# lichtenstein_controller.net
KiCad netlist of a schematic drawn in EAGLE
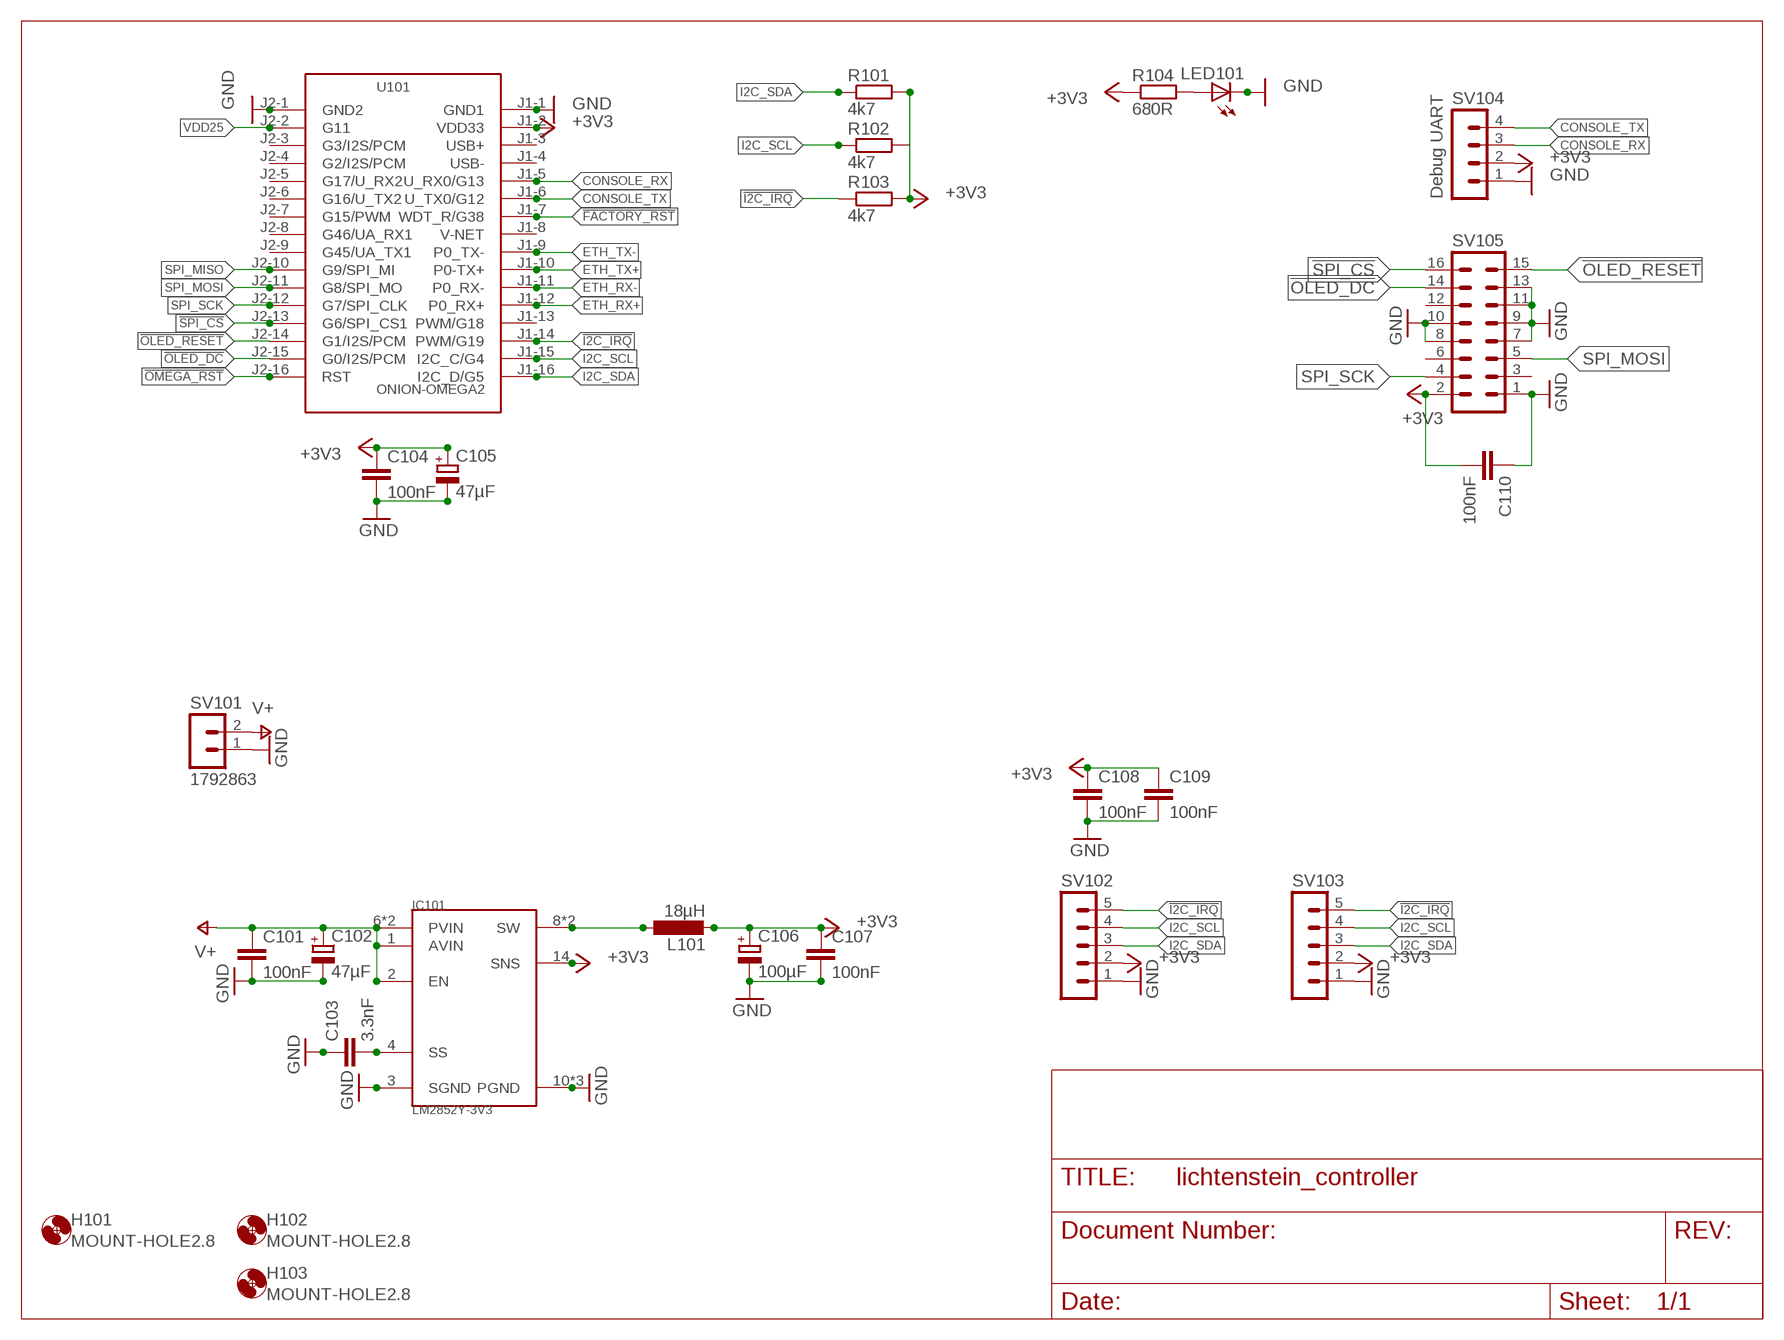
[diagram p0: schematic, sheet 1]

(export (version "E")
  (design (tool "Eeschema 10.0.6"))
  (components
    (comp (ref "C101")
      (value "100nF")
      (footprint "eagle-import:C0805")
      (libsource (lib "eagle-import") (part "C-EUC0805"))
    )
    (comp (ref "C102")
      (value "47µF")
      (footprint "eagle-import:CT7343")
      (libsource (lib "eagle-import") (part "CPOL-EUCT7343"))
    )
    (comp (ref "C103")
      (value "3.3nF")
      (footprint "eagle-import:C0805")
      (libsource (lib "eagle-import") (part "C-EUC0805"))
    )
    (comp (ref "C104")
      (value "100nF")
      (footprint "eagle-import:C0805")
      (libsource (lib "eagle-import") (part "C-EUC0805"))
    )
    (comp (ref "C105")
      (value "47µF")
      (footprint "eagle-import:CT7343")
      (libsource (lib "eagle-import") (part "CPOL-EUCT7343"))
    )
    (comp (ref "C106")
      (value "100µF")
      (footprint "eagle-import:CT7343")
      (libsource (lib "eagle-import") (part "CPOL-EUCT7343"))
    )
    (comp (ref "C107")
      (value "100nF")
      (footprint "eagle-import:C0805")
      (libsource (lib "eagle-import") (part "C-EUC0805"))
    )
    (comp (ref "C108")
      (value "100nF")
      (footprint "eagle-import:C0805")
      (libsource (lib "eagle-import") (part "C-EUC0805"))
    )
    (comp (ref "C109")
      (value "100nF")
      (footprint "eagle-import:C0805")
      (libsource (lib "eagle-import") (part "C-EUC0805"))
    )
    (comp (ref "C110")
      (value "100nF")
      (footprint "eagle-import:C0805")
      (libsource (lib "eagle-import") (part "C-EUC0805"))
    )
    (comp (ref "H101")
      (value "MOUNT-HOLE2.8")
      (footprint "eagle-import:2,8")
      (libsource (lib "eagle-import") (part "MOUNT-HOLE2.8"))
    )
    (comp (ref "H102")
      (value "MOUNT-HOLE2.8")
      (footprint "eagle-import:2,8")
      (libsource (lib "eagle-import") (part "MOUNT-HOLE2.8"))
    )
    (comp (ref "H103")
      (value "MOUNT-HOLE2.8")
      (footprint "eagle-import:2,8")
      (libsource (lib "eagle-import") (part "MOUNT-HOLE2.8"))
    )
    (comp (ref "IC101")
      (value "LM2852Y-3V3")
      (footprint "eagle-import:HTSSOP14")
      (libsource (lib "eagle-import") (part "LM2852HTSSOP14"))
    )
    (comp (ref "L101")
      (value "18µH")
      (footprint "eagle-import:SRR1050A")
      (libsource (lib "eagle-import") (part "SRR1050A"))
    )
    (comp (ref "LED101")
      (value "LEDCHIPLED_1206")
      (footprint "eagle-import:CHIPLED_1206")
      (libsource (lib "eagle-import") (part "LEDCHIPLED_1206"))
    )
    (comp (ref "R101")
      (value "4k7")
      (footprint "eagle-import:M0805")
      (libsource (lib "eagle-import") (part "R-EU_M0805"))
    )
    (comp (ref "R102")
      (value "4k7")
      (footprint "eagle-import:M0805")
      (libsource (lib "eagle-import") (part "R-EU_M0805"))
    )
    (comp (ref "R103")
      (value "4k7")
      (footprint "eagle-import:M0805")
      (libsource (lib "eagle-import") (part "R-EU_M0805"))
    )
    (comp (ref "R104")
      (value "680R")
      (footprint "eagle-import:M0805")
      (libsource (lib "eagle-import") (part "R-EU_M0805"))
    )
    (comp (ref "SV101")
      (value "1792863")
      (footprint "eagle-import:1792863")
      (libsource (lib "eagle-import") (part "1792863"))
    )
    (comp (ref "SV102")
      (value "MA05-1")
      (footprint "eagle-import:MA05-1")
      (libsource (lib "eagle-import") (part "MA05-1"))
    )
    (comp (ref "SV103")
      (value "MA05-1")
      (footprint "eagle-import:MA05-1")
      (libsource (lib "eagle-import") (part "MA05-1"))
    )
    (comp (ref "SV104")
      (value "MA04-1")
      (footprint "eagle-import:MA04-1")
      (libsource (lib "eagle-import") (part "MA04-1"))
    )
    (comp (ref "SV105")
      (value "MA08-2")
      (footprint "eagle-import:MA08-2")
      (libsource (lib "eagle-import") (part "MA08-2"))
    )
    (comp (ref "U101")
      (value "ONION-OMEGA2")
      (footprint "eagle-import:ONION-2MM-2X16")
      (libsource (lib "eagle-import") (part "ONION-OMEGA2"))
    )
  )
  (nets
    (net (code "1") (name "+3V3") (class "Default")
      (node (ref "C104") (pin "1") (pinfunction "1_1") (pintype "passive"))
      (node (ref "C105") (pin "+") (pinfunction "+_+") (pintype "passive"))
      (node (ref "C106") (pin "+") (pinfunction "+_+") (pintype "passive"))
      (node (ref "C107") (pin "1") (pinfunction "1_1") (pintype "passive"))
      (node (ref "C108") (pin "1") (pinfunction "1_1") (pintype "passive"))
      (node (ref "C109") (pin "1") (pinfunction "1_1") (pintype "passive"))
      (node (ref "C110") (pin "2") (pinfunction "2_2") (pintype "passive"))
      (node (ref "IC101") (pin "14") (pinfunction "SNS_14") (pintype "bidirectional"))
      (node (ref "L101") (pin "P$2") (pinfunction "2_P$2") (pintype "passive"))
      (node (ref "R101") (pin "2") (pinfunction "2_2") (pintype "passive"))
      (node (ref "R102") (pin "2") (pinfunction "2_2") (pintype "passive"))
      (node (ref "R103") (pin "2") (pinfunction "2_2") (pintype "passive"))
      (node (ref "R104") (pin "1") (pinfunction "1_1") (pintype "passive"))
      (node (ref "SV102") (pin "2") (pinfunction "2_2") (pintype "passive"))
      (node (ref "SV103") (pin "2") (pinfunction "2_2") (pintype "passive"))
      (node (ref "SV104") (pin "2") (pinfunction "2_2") (pintype "passive"))
      (node (ref "SV105") (pin "2") (pinfunction "2_2") (pintype "passive"))
      (node (ref "U101") (pin "J1-2") (pinfunction "VDD33_J1-2") (pintype "bidirectional"))
    )
    (net (code "2") (name "/~{FACTORY_RST}") (class "Default")
      (node (ref "U101") (pin "J1-7") (pinfunction "WDT_R/G38_J1-7") (pintype "bidirectional"))
    )
    (net (code "3") (name "/~{I2C_IRQ}") (class "Default")
      (node (ref "R103") (pin "1") (pinfunction "1_1") (pintype "passive"))
      (node (ref "SV102") (pin "5") (pinfunction "5_5") (pintype "passive"))
      (node (ref "SV103") (pin "5") (pinfunction "5_5") (pintype "passive"))
      (node (ref "U101") (pin "J1-14") (pinfunction "PWM/G19_J1-14") (pintype "bidirectional"))
    )
    (net (code "4") (name "/~{OLED_DC}") (class "Default")
      (node (ref "SV105") (pin "14") (pinfunction "14_14") (pintype "passive"))
      (node (ref "U101") (pin "J2-15") (pinfunction "G0/I2S/PCM_J2-15") (pintype "bidirectional"))
    )
    (net (code "5") (name "/~{OLED_RESET}") (class "Default")
      (node (ref "SV105") (pin "15") (pinfunction "15_15") (pintype "passive"))
      (node (ref "U101") (pin "J2-14") (pinfunction "G1/I2S/PCM_J2-14") (pintype "bidirectional"))
    )
    (net (code "6") (name "/~{OMEGA_RST}") (class "Default")
      (node (ref "U101") (pin "J2-16") (pinfunction "RST_J2-16") (pintype "bidirectional"))
    )
    (net (code "7") (name "/~{SPI_CS}") (class "Default")
      (node (ref "SV105") (pin "16") (pinfunction "16_16") (pintype "passive"))
      (node (ref "U101") (pin "J2-13") (pinfunction "G6/SPI_CS1_J2-13") (pintype "bidirectional"))
    )
    (net (code "8") (name "CONSOLE_RX") (class "Default")
      (node (ref "SV104") (pin "3") (pinfunction "3_3") (pintype "passive"))
      (node (ref "U101") (pin "J1-5") (pinfunction "U_RX0/G13_J1-5") (pintype "bidirectional"))
    )
    (net (code "9") (name "CONSOLE_TX") (class "Default")
      (node (ref "SV104") (pin "4") (pinfunction "4_4") (pintype "passive"))
      (node (ref "U101") (pin "J1-6") (pinfunction "U_TX0/G12_J1-6") (pintype "bidirectional"))
    )
    (net (code "10") (name "ETH_RX+") (class "Default")
      (node (ref "U101") (pin "J1-12") (pinfunction "P0_RX+_J1-12") (pintype "bidirectional"))
    )
    (net (code "11") (name "ETH_RX-") (class "Default")
      (node (ref "U101") (pin "J1-11") (pinfunction "P0_RX-_J1-11") (pintype "bidirectional"))
    )
    (net (code "12") (name "ETH_TX+") (class "Default")
      (node (ref "U101") (pin "J1-10") (pinfunction "P0-TX+_J1-10") (pintype "bidirectional"))
    )
    (net (code "13") (name "ETH_TX-") (class "Default")
      (node (ref "U101") (pin "J1-9") (pinfunction "P0_TX-_J1-9") (pintype "bidirectional"))
    )
    (net (code "14") (name "GND") (class "Default")
      (node (ref "C101") (pin "2") (pinfunction "2_2") (pintype "passive"))
      (node (ref "C102") (pin "-") (pinfunction "-_-") (pintype "passive"))
      (node (ref "C103") (pin "1") (pinfunction "1_1") (pintype "passive"))
      (node (ref "C104") (pin "2") (pinfunction "2_2") (pintype "passive"))
      (node (ref "C105") (pin "-") (pinfunction "-_-") (pintype "passive"))
      (node (ref "C106") (pin "-") (pinfunction "-_-") (pintype "passive"))
      (node (ref "C107") (pin "2") (pinfunction "2_2") (pintype "passive"))
      (node (ref "C108") (pin "2") (pinfunction "2_2") (pintype "passive"))
      (node (ref "C109") (pin "2") (pinfunction "2_2") (pintype "passive"))
      (node (ref "C110") (pin "1") (pinfunction "1_1") (pintype "passive"))
      (node (ref "IC101") (pin "10") (pinfunction "PGND_10") (pintype "power_in"))
      (node (ref "IC101") (pin "11") (pinfunction "PGND_11") (pintype "power_in"))
      (node (ref "IC101") (pin "3") (pinfunction "SGND_3") (pintype "power_in"))
      (node (ref "IC101") (pin "PAD") (pinfunction "PGND_PAD") (pintype "power_in"))
      (node (ref "LED101") (pin "C") (pinfunction "C_C") (pintype "passive"))
      (node (ref "SV101") (pin "1") (pinfunction "1_1") (pintype "passive"))
      (node (ref "SV102") (pin "1") (pinfunction "1_1") (pintype "passive"))
      (node (ref "SV103") (pin "1") (pinfunction "1_1") (pintype "passive"))
      (node (ref "SV104") (pin "1") (pinfunction "1_1") (pintype "passive"))
      (node (ref "SV105") (pin "1") (pinfunction "1_1") (pintype "passive"))
      (node (ref "SV105") (pin "10") (pinfunction "10_10") (pintype "passive"))
      (node (ref "SV105") (pin "11") (pinfunction "11_11") (pintype "passive"))
      (node (ref "SV105") (pin "13") (pinfunction "13_13") (pintype "passive"))
      (node (ref "SV105") (pin "7") (pinfunction "7_7") (pintype "passive"))
      (node (ref "SV105") (pin "8") (pinfunction "8_8") (pintype "passive"))
      (node (ref "SV105") (pin "9") (pinfunction "9_9") (pintype "passive"))
      (node (ref "U101") (pin "J1-1") (pinfunction "GND1_J1-1") (pintype "bidirectional"))
      (node (ref "U101") (pin "J2-1") (pinfunction "GND2_J2-1") (pintype "bidirectional"))
    )
    (net (code "15") (name "I2C_SCL") (class "Default")
      (node (ref "R102") (pin "1") (pinfunction "1_1") (pintype "passive"))
      (node (ref "SV102") (pin "4") (pinfunction "4_4") (pintype "passive"))
      (node (ref "SV103") (pin "4") (pinfunction "4_4") (pintype "passive"))
      (node (ref "U101") (pin "J1-15") (pinfunction "I2C_C/G4_J1-15") (pintype "bidirectional"))
    )
    (net (code "16") (name "I2C_SDA") (class "Default")
      (node (ref "R101") (pin "1") (pinfunction "1_1") (pintype "passive"))
      (node (ref "SV102") (pin "3") (pinfunction "3_3") (pintype "passive"))
      (node (ref "SV103") (pin "3") (pinfunction "3_3") (pintype "passive"))
      (node (ref "U101") (pin "J1-16") (pinfunction "I2C_D/G5_J1-16") (pintype "bidirectional"))
    )
    (net (code "17") (name "Net-(IC101-SS)") (class "Default")
      (node (ref "C103") (pin "2") (pinfunction "2_2") (pintype "passive"))
      (node (ref "IC101") (pin "4") (pinfunction "SS_4") (pintype "bidirectional"))
    )
    (net (code "18") (name "Net-(L101-1)") (class "Default")
      (node (ref "IC101") (pin "8") (pinfunction "SW_8") (pintype "bidirectional"))
      (node (ref "IC101") (pin "9") (pinfunction "SW_9") (pintype "bidirectional"))
      (node (ref "L101") (pin "P$1") (pinfunction "1_P$1") (pintype "passive"))
    )
    (net (code "19") (name "Net-(LED101-PadA)") (class "Default")
      (node (ref "LED101") (pin "A") (pinfunction "A_A") (pintype "passive"))
      (node (ref "R104") (pin "2") (pinfunction "2_2") (pintype "passive"))
    )
    (net (code "20") (name "SPI_MISO") (class "Default")
      (node (ref "U101") (pin "J2-10") (pinfunction "G9/SPI_MI_J2-10") (pintype "bidirectional"))
    )
    (net (code "21") (name "SPI_MOSI") (class "Default")
      (node (ref "SV105") (pin "5") (pinfunction "5_5") (pintype "passive"))
      (node (ref "U101") (pin "J2-11") (pinfunction "G8/SPI_MO_J2-11") (pintype "bidirectional"))
    )
    (net (code "22") (name "SPI_SCK") (class "Default")
      (node (ref "SV105") (pin "4") (pinfunction "4_4") (pintype "passive"))
      (node (ref "U101") (pin "J2-12") (pinfunction "G7/SPI_CLK_J2-12") (pintype "bidirectional"))
    )
    (net (code "23") (name "V+") (class "Default")
      (node (ref "C101") (pin "1") (pinfunction "1_1") (pintype "passive"))
      (node (ref "C102") (pin "+") (pinfunction "+_+") (pintype "passive"))
      (node (ref "IC101") (pin "1") (pinfunction "AVIN_1") (pintype "power_in"))
      (node (ref "IC101") (pin "2") (pinfunction "EN_2") (pintype "input"))
      (node (ref "IC101") (pin "6") (pinfunction "PVIN_6") (pintype "power_in"))
      (node (ref "IC101") (pin "7") (pinfunction "PVIN_7") (pintype "power_in"))
      (node (ref "SV101") (pin "2") (pinfunction "2_2") (pintype "passive"))
    )
    (net (code "24") (name "VDD25") (class "Default")
      (node (ref "U101") (pin "J2-2") (pinfunction "G11_J2-2") (pintype "bidirectional"))
    )
    (net (code "25") (name "unconnected-(SV105-Pad3)") (class "Default")
      (node (ref "SV105") (pin "3") (pinfunction "3_3") (pintype "passive"))
    )
    (net (code "26") (name "unconnected-(SV105-Pad6)") (class "Default")
      (node (ref "SV105") (pin "6") (pinfunction "6_6") (pintype "passive"))
    )
    (net (code "27") (name "unconnected-(SV105-Pad12)") (class "Default")
      (node (ref "SV105") (pin "12") (pinfunction "12_12") (pintype "passive"))
    )
    (net (code "28") (name "unconnected-(U101-G2{slash}I2S{slash}PCM-PadJ2-4)") (class "Default")
      (node (ref "U101") (pin "J2-4") (pinfunction "G2/I2S/PCM_J2-4") (pintype "bidirectional"))
    )
    (net (code "29") (name "unconnected-(U101-G3{slash}I2S{slash}PCM-PadJ2-3)") (class "Default")
      (node (ref "U101") (pin "J2-3") (pinfunction "G3/I2S/PCM_J2-3") (pintype "bidirectional"))
    )
    (net (code "30") (name "unconnected-(U101-G15{slash}PWM-PadJ2-7)") (class "Default")
      (node (ref "U101") (pin "J2-7") (pinfunction "G15/PWM_J2-7") (pintype "bidirectional"))
    )
    (net (code "31") (name "unconnected-(U101-G16{slash}U_TX2-PadJ2-6)") (class "Default")
      (node (ref "U101") (pin "J2-6") (pinfunction "G16/U_TX2_J2-6") (pintype "bidirectional"))
    )
    (net (code "32") (name "unconnected-(U101-G17{slash}U_RX2-PadJ2-5)") (class "Default")
      (node (ref "U101") (pin "J2-5") (pinfunction "G17/U_RX2_J2-5") (pintype "bidirectional"))
    )
    (net (code "33") (name "unconnected-(U101-G45{slash}UA_TX1-PadJ2-9)") (class "Default")
      (node (ref "U101") (pin "J2-9") (pinfunction "G45/UA_TX1_J2-9") (pintype "bidirectional"))
    )
    (net (code "34") (name "unconnected-(U101-G46{slash}UA_RX1-PadJ2-8)") (class "Default")
      (node (ref "U101") (pin "J2-8") (pinfunction "G46/UA_RX1_J2-8") (pintype "bidirectional"))
    )
    (net (code "35") (name "unconnected-(U101-PWM{slash}G18-PadJ1-13)") (class "Default")
      (node (ref "U101") (pin "J1-13") (pinfunction "PWM/G18_J1-13") (pintype "bidirectional"))
    )
    (net (code "36") (name "unconnected-(U101-USB+-PadJ1-3)") (class "Default")
      (node (ref "U101") (pin "J1-3") (pinfunction "USB+_J1-3") (pintype "bidirectional"))
    )
    (net (code "37") (name "unconnected-(U101-USB--PadJ1-4)") (class "Default")
      (node (ref "U101") (pin "J1-4") (pinfunction "USB-_J1-4") (pintype "bidirectional"))
    )
    (net (code "38") (name "unconnected-(U101-V-NET-PadJ1-8)") (class "Default")
      (node (ref "U101") (pin "J1-8") (pinfunction "V-NET_J1-8") (pintype "bidirectional"))
    )
  )
)
